# V6_2.net
KiCad netlist of a schematic drawn in Altium Designer
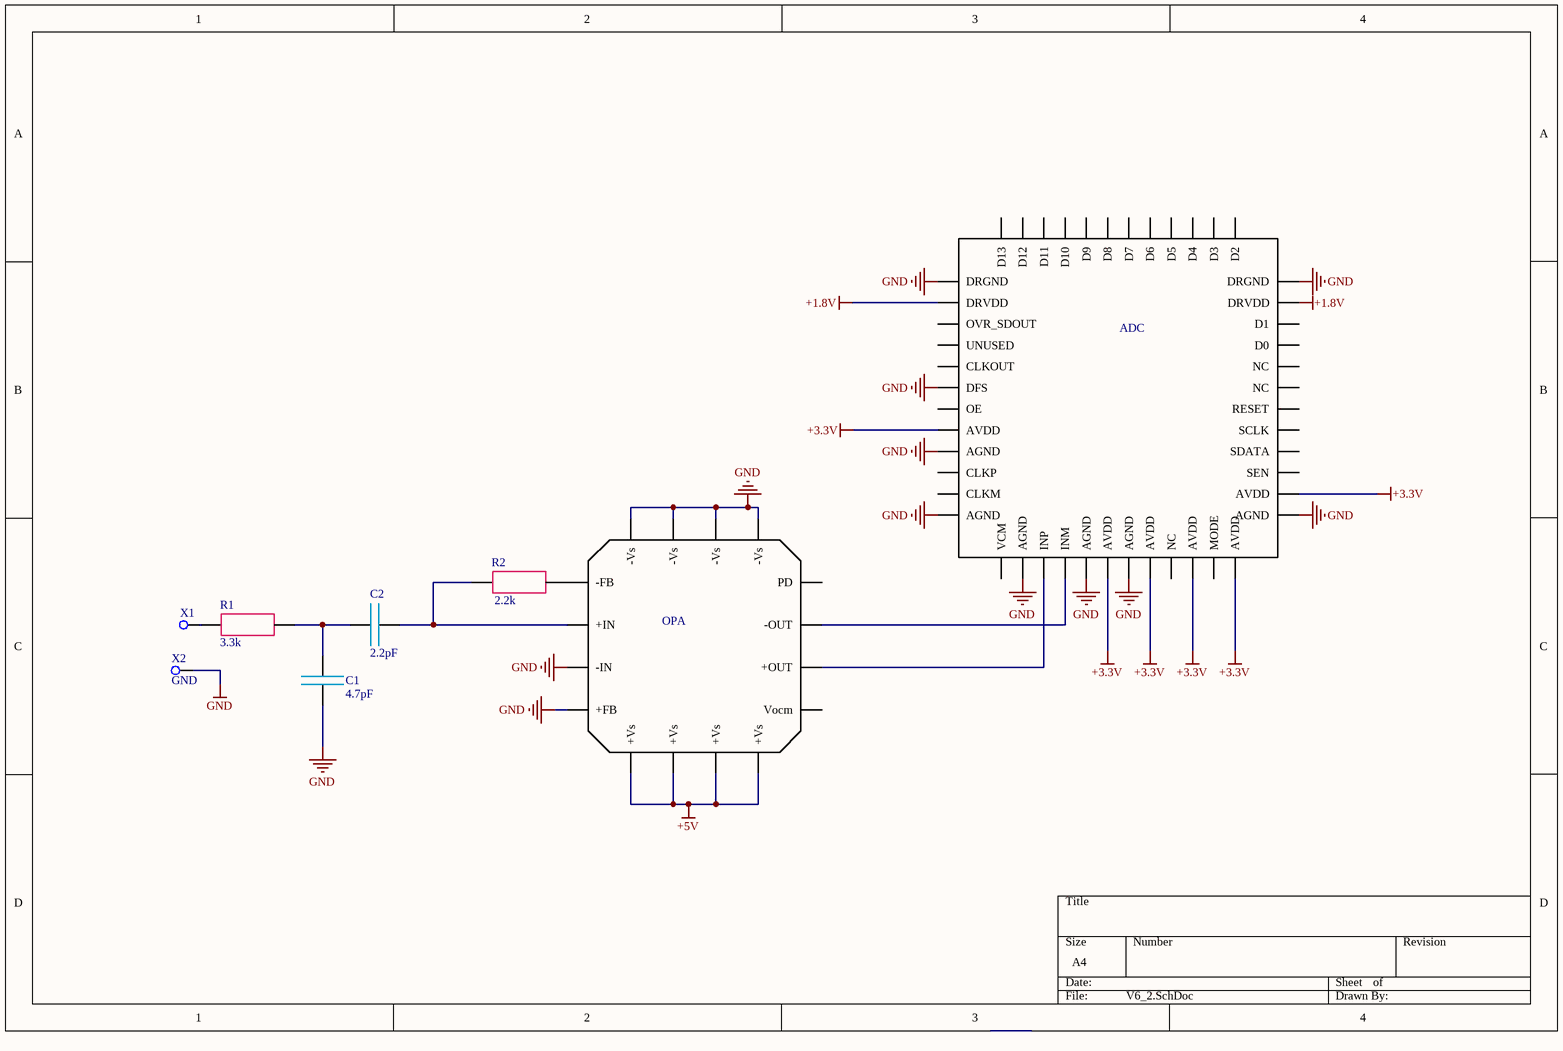
[diagram p0: V6_2.SchDoc]

(export (version "E")
  (design (tool "Eeschema 10.0.6"))
  (components
    (comp (ref "ADC") (value "ADS") (footprint "ADS") (libsource (lib "V6_2") (part "ADS")))
    (comp (ref "C1") (value "4.7pF") (footprint "con") (libsource (lib "V6_2") (part "Condenser1")))
    (comp (ref "C2") (value "2.2pF") (footprint "con") (libsource (lib "V6_2") (part "Condenser1")))
    (comp (ref "OPA") (value "OPA") (footprint "OPA") (libsource (lib "V6_2") (part "ADA")))
    (comp (ref "R1") (value "3.3k") (footprint "Rezistor") (libsource (lib "V6_2") (part "Resistor1")))
    (comp (ref "R2") (value "2.2k") (footprint "Rezistor") (libsource (lib "V6_2") (part "Resistor1")))
    (comp (ref "X1") (value "~") (footprint "DRL10") (libsource (lib "V2_1") (part "DRL")))
    (comp (ref "X2") (value "GND") (footprint "DRL10") (libsource (lib "V2_1") (part "DRL")))
  )
  (nets
    (net (code "1") (name "+1.8V") (class "Default")
      (node (ref "ADC") (pin "2") (pinfunction "DRVDD_2") (pintype "passive"))
      (node (ref "ADC") (pin "35") (pinfunction "DRVDD_35") (pintype "passive"))
    )
    (net (code "2") (name "+3.3V") (class "Default")
      (node (ref "ADC") (pin "18") (pinfunction "AVDD_18") (pintype "passive"))
      (node (ref "ADC") (pin "20") (pinfunction "AVDD_20") (pintype "passive"))
      (node (ref "ADC") (pin "22") (pinfunction "AVDD_22") (pintype "passive"))
      (node (ref "ADC") (pin "24") (pinfunction "AVDD_24") (pintype "passive"))
      (node (ref "ADC") (pin "26") (pinfunction "AVDD_26") (pintype "passive"))
      (node (ref "ADC") (pin "8") (pinfunction "AVDD_8") (pintype "passive"))
    )
    (net (code "3") (name "+5V") (class "Default")
      (node (ref "OPA") (pin "5") (pinfunction "+Vs_5") (pintype "passive"))
      (node (ref "OPA") (pin "6") (pinfunction "+Vs_6") (pintype "passive"))
      (node (ref "OPA") (pin "7") (pinfunction "+Vs_7") (pintype "passive"))
      (node (ref "OPA") (pin "8") (pinfunction "+Vs_8") (pintype "passive"))
    )
    (net (code "4") (name "GND") (class "Default")
      (node (ref "ADC") (pin "1") (pinfunction "DRGND_1") (pintype "passive"))
      (node (ref "ADC") (pin "12") (pinfunction "AGND_12") (pintype "passive"))
      (node (ref "ADC") (pin "14") (pinfunction "AGND_14") (pintype "passive"))
      (node (ref "ADC") (pin "17") (pinfunction "AGND_17") (pintype "passive"))
      (node (ref "ADC") (pin "19") (pinfunction "AGND_19") (pintype "passive"))
      (node (ref "ADC") (pin "25") (pinfunction "AGND_25") (pintype "passive"))
      (node (ref "ADC") (pin "36") (pinfunction "DRGND_36") (pintype "passive"))
      (node (ref "ADC") (pin "6") (pinfunction "DFS_6") (pintype "passive"))
      (node (ref "ADC") (pin "9") (pinfunction "AGND_9") (pintype "passive"))
      (node (ref "C1") (pin "1") (pinfunction "1_1") (pintype "passive"))
      (node (ref "OPA") (pin "13") (pinfunction "-Vs_13") (pintype "passive"))
      (node (ref "OPA") (pin "14") (pinfunction "-Vs_14") (pintype "passive"))
      (node (ref "OPA") (pin "15") (pinfunction "-Vs_15") (pintype "passive"))
      (node (ref "OPA") (pin "16") (pinfunction "-Vs_16") (pintype "passive"))
      (node (ref "OPA") (pin "3") (pinfunction "-IN_3") (pintype "passive"))
      (node (ref "OPA") (pin "4") (pinfunction "+FB_4") (pintype "passive"))
      (node (ref "X2") (pin "DRIL") (pinfunction "DRIL_DRIL") (pintype "passive"))
    )
    (net (code "5") (name "Net-(ADC-INM)") (class "Default")
      (node (ref "ADC") (pin "16") (pinfunction "INM_16") (pintype "passive"))
      (node (ref "OPA") (pin "11") (pinfunction "-OUT_11") (pintype "passive"))
    )
    (net (code "6") (name "Net-(ADC-INP)") (class "Default")
      (node (ref "ADC") (pin "15") (pinfunction "INP_15") (pintype "passive"))
      (node (ref "OPA") (pin "10") (pinfunction "+OUT_10") (pintype "passive"))
    )
    (net (code "7") (name "Net-(C1-Pad2)") (class "Default")
      (node (ref "C1") (pin "2") (pinfunction "2_2") (pintype "passive"))
      (node (ref "C2") (pin "1") (pinfunction "1_1") (pintype "passive"))
      (node (ref "R1") (pin "2") (pinfunction "2_2") (pintype "passive"))
    )
    (net (code "8") (name "Net-(OPA-+IN)") (class "Default")
      (node (ref "C2") (pin "2") (pinfunction "2_2") (pintype "passive"))
      (node (ref "OPA") (pin "2") (pinfunction "+IN_2") (pintype "passive"))
      (node (ref "R2") (pin "1") (pinfunction "1_1") (pintype "passive"))
    )
    (net (code "9") (name "Net-(OPA--FB)") (class "Default")
      (node (ref "OPA") (pin "1") (pinfunction "-FB_1") (pintype "passive"))
      (node (ref "R2") (pin "2") (pinfunction "2_2") (pintype "passive"))
    )
    (net (code "10") (name "Net-(R1-Pad1)") (class "Default")
      (node (ref "R1") (pin "1") (pinfunction "1_1") (pintype "passive"))
      (node (ref "X1") (pin "DRIL") (pinfunction "DRIL_DRIL") (pintype "passive"))
    )
    (net (code "11") (name "unconnected-(ADC-CLKM-Pad11)") (class "Default")
      (node (ref "ADC") (pin "11") (pinfunction "CLKM_11") (pintype "passive"))
    )
    (net (code "12") (name "unconnected-(ADC-CLKOUT-Pad5)") (class "Default")
      (node (ref "ADC") (pin "5") (pinfunction "CLKOUT_5") (pintype "passive"))
    )
    (net (code "13") (name "unconnected-(ADC-CLKP-Pad10)") (class "Default")
      (node (ref "ADC") (pin "10") (pinfunction "CLKP_10") (pintype "passive"))
    )
    (net (code "14") (name "unconnected-(ADC-D0-Pad33)") (class "Default")
      (node (ref "ADC") (pin "33") (pinfunction "D0_33") (pintype "passive"))
    )
    (net (code "15") (name "unconnected-(ADC-D1-Pad34)") (class "Default")
      (node (ref "ADC") (pin "34") (pinfunction "D1_34") (pintype "passive"))
    )
    (net (code "16") (name "unconnected-(ADC-D2-Pad37)") (class "Default")
      (node (ref "ADC") (pin "37") (pinfunction "D2_37") (pintype "passive"))
    )
    (net (code "17") (name "unconnected-(ADC-D3-Pad38)") (class "Default")
      (node (ref "ADC") (pin "38") (pinfunction "D3_38") (pintype "passive"))
    )
    (net (code "18") (name "unconnected-(ADC-D4-Pad39)") (class "Default")
      (node (ref "ADC") (pin "39") (pinfunction "D4_39") (pintype "passive"))
    )
    (net (code "19") (name "unconnected-(ADC-D5-Pad40)") (class "Default")
      (node (ref "ADC") (pin "40") (pinfunction "D5_40") (pintype "passive"))
    )
    (net (code "20") (name "unconnected-(ADC-D6-Pad41)") (class "Default")
      (node (ref "ADC") (pin "41") (pinfunction "D6_41") (pintype "passive"))
    )
    (net (code "21") (name "unconnected-(ADC-D7-Pad42)") (class "Default")
      (node (ref "ADC") (pin "42") (pinfunction "D7_42") (pintype "passive"))
    )
    (net (code "22") (name "unconnected-(ADC-D8-Pad43)") (class "Default")
      (node (ref "ADC") (pin "43") (pinfunction "D8_43") (pintype "passive"))
    )
    (net (code "23") (name "unconnected-(ADC-D9-Pad44)") (class "Default")
      (node (ref "ADC") (pin "44") (pinfunction "D9_44") (pintype "passive"))
    )
    (net (code "24") (name "unconnected-(ADC-D10-Pad45)") (class "Default")
      (node (ref "ADC") (pin "45") (pinfunction "D10_45") (pintype "passive"))
    )
    (net (code "25") (name "unconnected-(ADC-D11-Pad46)") (class "Default")
      (node (ref "ADC") (pin "46") (pinfunction "D11_46") (pintype "passive"))
    )
    (net (code "26") (name "unconnected-(ADC-D12-Pad47)") (class "Default")
      (node (ref "ADC") (pin "47") (pinfunction "D12_47") (pintype "passive"))
    )
    (net (code "27") (name "unconnected-(ADC-D13-Pad48)") (class "Default")
      (node (ref "ADC") (pin "48") (pinfunction "D13_48") (pintype "passive"))
    )
    (net (code "28") (name "unconnected-(ADC-MODE-Pad23)") (class "Default")
      (node (ref "ADC") (pin "23") (pinfunction "MODE_23") (pintype "passive"))
    )
    (net (code "29") (name "unconnected-(ADC-NC-Pad21)") (class "Default")
      (node (ref "ADC") (pin "21") (pinfunction "NC_21") (pintype "passive"))
    )
    (net (code "30") (name "unconnected-(ADC-NC-Pad31)") (class "Default")
      (node (ref "ADC") (pin "31") (pinfunction "NC_31") (pintype "passive"))
    )
    (net (code "31") (name "unconnected-(ADC-NC-Pad32)") (class "Default")
      (node (ref "ADC") (pin "32") (pinfunction "NC_32") (pintype "passive"))
    )
    (net (code "32") (name "unconnected-(ADC-OE-Pad7)") (class "Default")
      (node (ref "ADC") (pin "7") (pinfunction "OE_7") (pintype "passive"))
    )
    (net (code "33") (name "unconnected-(ADC-OVR_SDOUT-Pad3)") (class "Default")
      (node (ref "ADC") (pin "3") (pinfunction "OVR_SDOUT_3") (pintype "passive"))
    )
    (net (code "34") (name "unconnected-(ADC-RESET-Pad30)") (class "Default")
      (node (ref "ADC") (pin "30") (pinfunction "RESET_30") (pintype "passive"))
    )
    (net (code "35") (name "unconnected-(ADC-SCLK-Pad29)") (class "Default")
      (node (ref "ADC") (pin "29") (pinfunction "SCLK_29") (pintype "passive"))
    )
    (net (code "36") (name "unconnected-(ADC-SDATA-Pad28)") (class "Default")
      (node (ref "ADC") (pin "28") (pinfunction "SDATA_28") (pintype "passive"))
    )
    (net (code "37") (name "unconnected-(ADC-SEN-Pad27)") (class "Default")
      (node (ref "ADC") (pin "27") (pinfunction "SEN_27") (pintype "passive"))
    )
    (net (code "38") (name "unconnected-(ADC-UNUSED-Pad4)") (class "Default")
      (node (ref "ADC") (pin "4") (pinfunction "UNUSED_4") (pintype "passive"))
    )
    (net (code "39") (name "unconnected-(ADC-VCM-Pad13)") (class "Default")
      (node (ref "ADC") (pin "13") (pinfunction "VCM_13") (pintype "passive"))
    )
    (net (code "40") (name "unconnected-(OPA-PD-Pad12)") (class "Default")
      (node (ref "OPA") (pin "12") (pinfunction "PD_12") (pintype "passive"))
    )
    (net (code "41") (name "unconnected-(OPA-Vocm-Pad9)") (class "Default")
      (node (ref "OPA") (pin "9") (pinfunction "Vocm_9") (pintype "passive"))
    )
  )
)
